# STM32.net
KiCad netlist of a schematic drawn in Altium Designer
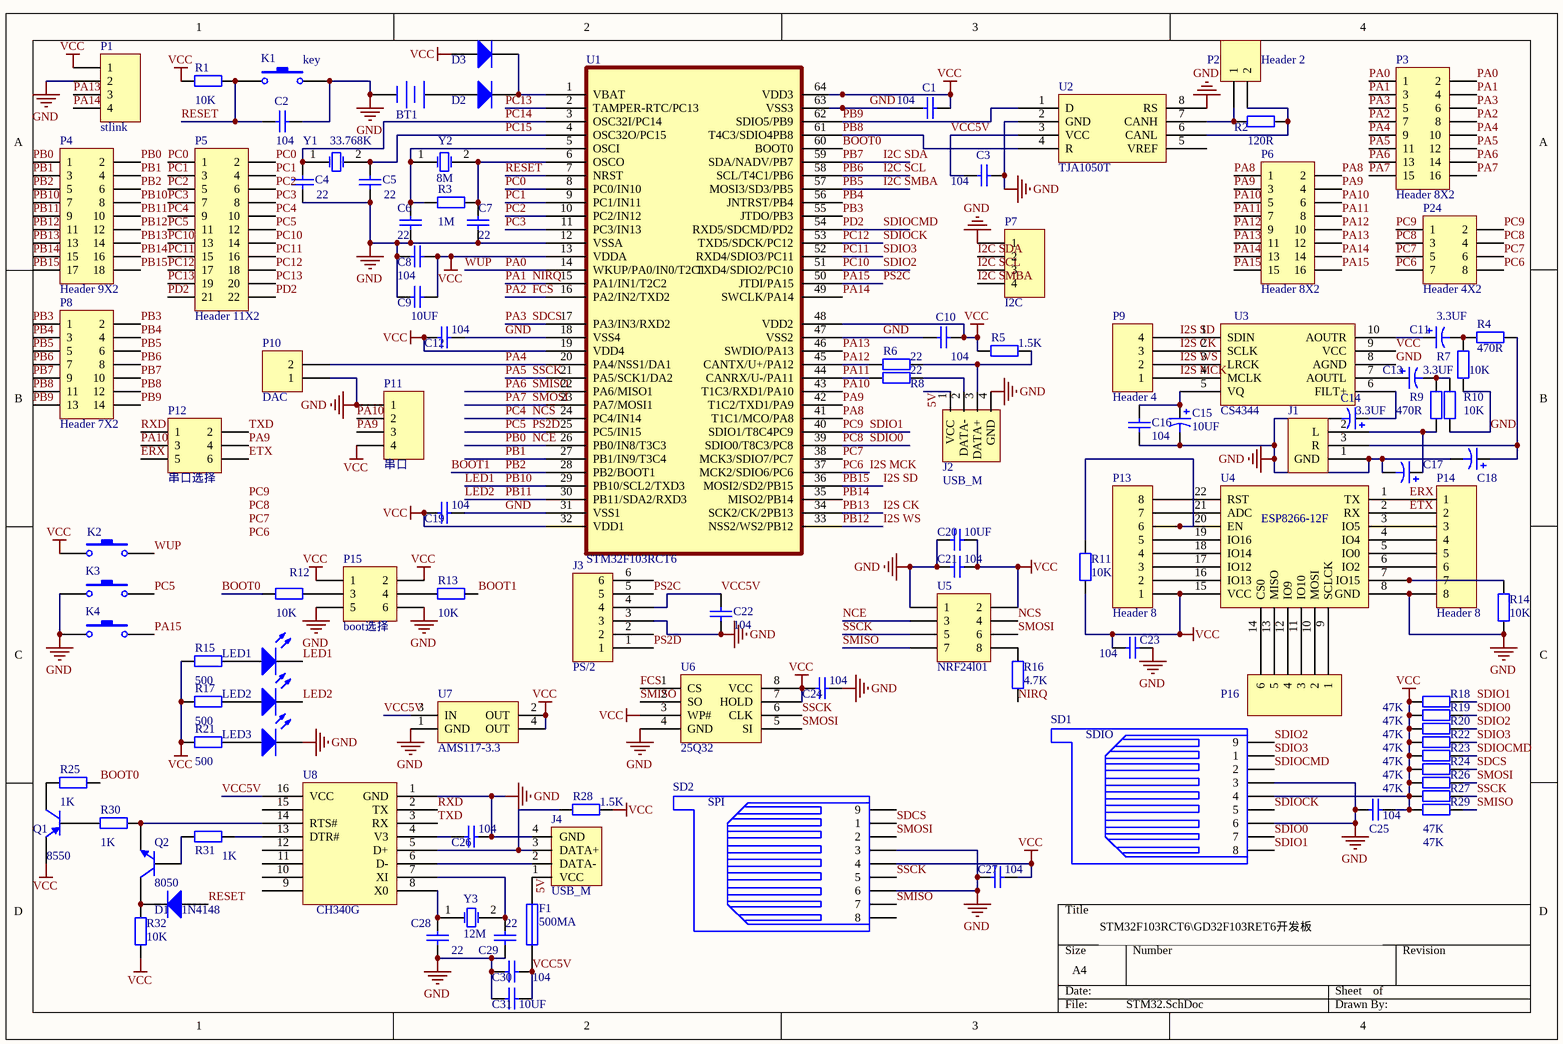
[diagram p0: STM32.SchDoc]

(export (version "E")
  (design (tool "Eeschema 10.0.6"))
  (components
    (comp (ref "BT1") (value "电池") (footprint "电池座") (libsource (lib "SCH封装库") (part "电池")))
    (comp (ref "C1")
      (value "104")
      (footprint "6-0805_N")
      (description "Capacitor")
      (fields (field (name "Comment") "Cap") (field (name "PUBLISHER") "Altium Limited"))
      (libsource (lib "Miscellaneous Devices") (part "Cap"))
    )
    (comp (ref "C2")
      (value "104")
      (footprint "6-0805_N")
      (description "Capacitor")
      (fields (field (name "Comment") "Cap") (field (name "PUBLISHER") "Altium Limited"))
      (libsource (lib "Miscellaneous Devices") (part "Cap"))
    )
    (comp (ref "C3")
      (value "104")
      (footprint "6-0805_N")
      (description "Capacitor")
      (fields (field (name "Comment") "Cap") (field (name "PUBLISHER") "Altium Limited"))
      (libsource (lib "Miscellaneous Devices") (part "Cap"))
    )
    (comp (ref "C4")
      (value "22")
      (footprint "6-0805_N")
      (description "Capacitor")
      (fields (field (name "Comment") "Cap") (field (name "PUBLISHER") "Altium Limited"))
      (libsource (lib "Miscellaneous Devices") (part "Cap"))
    )
    (comp (ref "C5")
      (value "22")
      (footprint "6-0805_N")
      (description "Capacitor")
      (fields (field (name "Comment") "Cap") (field (name "PUBLISHER") "Altium Limited"))
      (libsource (lib "Miscellaneous Devices") (part "Cap"))
    )
    (comp (ref "C6")
      (value "22")
      (footprint "6-0805_N")
      (description "Capacitor")
      (fields (field (name "Comment") "Cap") (field (name "PUBLISHER") "Altium Limited"))
      (libsource (lib "Miscellaneous Devices") (part "Cap"))
    )
    (comp (ref "C7")
      (value "22")
      (footprint "6-0805_N")
      (description "Capacitor")
      (fields (field (name "Comment") "Cap") (field (name "PUBLISHER") "Altium Limited"))
      (libsource (lib "Miscellaneous Devices") (part "Cap"))
    )
    (comp (ref "C8")
      (value "104")
      (footprint "6-0805_N")
      (description "Capacitor")
      (fields (field (name "Comment") "Cap") (field (name "PUBLISHER") "Altium Limited"))
      (libsource (lib "Miscellaneous Devices") (part "Cap"))
    )
    (comp (ref "C9")
      (value "10UF")
      (footprint "6-0805_N")
      (description "Capacitor")
      (fields (field (name "Comment") "Cap") (field (name "PUBLISHER") "Altium Limited"))
      (libsource (lib "Miscellaneous Devices") (part "Cap"))
    )
    (comp (ref "C10")
      (value "104")
      (footprint "6-0805_N")
      (description "Capacitor")
      (fields (field (name "Comment") "Cap") (field (name "PUBLISHER") "Altium Limited"))
      (libsource (lib "Miscellaneous Devices") (part "Cap"))
    )
    (comp (ref "C11")
      (value "3.3UF")
      (footprint "极性电容")
      (description "Polarized Capacitor (Surface Mount)")
      (fields (field (name "Comment") "Cap Pol3") (field (name "PUBLISHER") "Altium Limited"))
      (libsource (lib "Miscellaneous Devices") (part "Cap Pol3"))
    )
    (comp (ref "C12")
      (value "104")
      (footprint "6-0805_N")
      (description "Capacitor")
      (fields (field (name "Comment") "Cap") (field (name "PUBLISHER") "Altium Limited"))
      (libsource (lib "Miscellaneous Devices") (part "Cap"))
    )
    (comp (ref "C13")
      (value "3.3UF")
      (footprint "极性电容")
      (description "Polarized Capacitor (Surface Mount)")
      (fields (field (name "Comment") "Cap Pol3") (field (name "PUBLISHER") "Altium Limited"))
      (libsource (lib "Miscellaneous Devices") (part "Cap Pol3"))
    )
    (comp (ref "C14")
      (value "3.3UF")
      (footprint "极性电容")
      (description "Polarized Capacitor (Surface Mount)")
      (fields (field (name "Comment") "Cap Pol3") (field (name "PUBLISHER") "Altium Limited"))
      (libsource (lib "Miscellaneous Devices") (part "Cap Pol3"))
    )
    (comp (ref "C15")
      (value "10UF")
      (footprint "极性电容")
      (description "Polarized Capacitor (Surface Mount)")
      (fields (field (name "Comment") "Cap Pol3") (field (name "PUBLISHER") "Altium Limited"))
      (libsource (lib "Miscellaneous Devices") (part "Cap Pol3"))
    )
    (comp (ref "C16")
      (value "104")
      (footprint "6-0805_N")
      (description "Capacitor")
      (fields (field (name "Comment") "Cap") (field (name "PUBLISHER") "Altium Limited"))
      (libsource (lib "Miscellaneous Devices") (part "Cap"))
    )
    (comp (ref "C17")
      (value "Cap Pol3")
      (footprint "极性电容")
      (description "Polarized Capacitor (Surface Mount)")
      (fields (field (name "PUBLISHER") "Altium Limited"))
      (libsource (lib "Miscellaneous Devices") (part "Cap Pol3"))
    )
    (comp (ref "C18")
      (value "Cap Pol3")
      (footprint "极性电容")
      (description "Polarized Capacitor (Surface Mount)")
      (fields (field (name "PUBLISHER") "Altium Limited"))
      (libsource (lib "Miscellaneous Devices") (part "Cap Pol3"))
    )
    (comp (ref "C19")
      (value "104")
      (footprint "6-0805_N")
      (description "Capacitor")
      (fields (field (name "Comment") "Cap") (field (name "PUBLISHER") "Altium Limited"))
      (libsource (lib "Miscellaneous Devices") (part "Cap"))
    )
    (comp (ref "C20")
      (value "10UF")
      (footprint "6-0805_N")
      (description "Capacitor")
      (fields (field (name "Comment") "Cap") (field (name "PUBLISHER") "Altium Limited"))
      (libsource (lib "Miscellaneous Devices") (part "Cap"))
    )
    (comp (ref "C21")
      (value "104")
      (footprint "6-0805_N")
      (description "Capacitor")
      (fields (field (name "Comment") "Cap") (field (name "PUBLISHER") "Altium Limited"))
      (libsource (lib "Miscellaneous Devices") (part "Cap"))
    )
    (comp (ref "C22")
      (value "104")
      (footprint "6-0805_N")
      (description "Capacitor")
      (fields (field (name "Comment") "Cap") (field (name "PUBLISHER") "Altium Limited"))
      (libsource (lib "Miscellaneous Devices") (part "Cap"))
    )
    (comp (ref "C23")
      (value "104")
      (footprint "6-0805_N")
      (description "Capacitor")
      (fields (field (name "Comment") "Cap") (field (name "PUBLISHER") "Altium Limited"))
      (libsource (lib "Miscellaneous Devices") (part "Cap"))
    )
    (comp (ref "C24")
      (value "104")
      (footprint "6-0805_N")
      (description "Capacitor")
      (fields (field (name "Comment") "Cap") (field (name "PUBLISHER") "Altium Limited"))
      (libsource (lib "Miscellaneous Devices") (part "Cap"))
    )
    (comp (ref "C25")
      (value "104")
      (footprint "6-0805_N")
      (description "Capacitor")
      (fields (field (name "Comment") "Cap") (field (name "PUBLISHER") "Altium Limited"))
      (libsource (lib "Miscellaneous Devices") (part "Cap"))
    )
    (comp (ref "C26")
      (value "104")
      (footprint "6-0805_N")
      (description "Capacitor")
      (fields (field (name "Comment") "Cap") (field (name "PUBLISHER") "Altium Limited"))
      (libsource (lib "Miscellaneous Devices") (part "Cap"))
    )
    (comp (ref "C27")
      (value "104")
      (footprint "6-0805_N")
      (description "Capacitor")
      (fields (field (name "Comment") "Cap") (field (name "PUBLISHER") "Altium Limited"))
      (libsource (lib "Miscellaneous Devices") (part "Cap"))
    )
    (comp (ref "C28")
      (value "22")
      (footprint "6-0805_N")
      (description "Capacitor")
      (fields (field (name "Comment") "Cap") (field (name "PUBLISHER") "Altium Limited"))
      (libsource (lib "Miscellaneous Devices") (part "Cap"))
    )
    (comp (ref "C29")
      (value "22")
      (footprint "6-0805_N")
      (description "Capacitor")
      (fields (field (name "Comment") "Cap") (field (name "PUBLISHER") "Altium Limited"))
      (libsource (lib "Miscellaneous Devices") (part "Cap"))
    )
    (comp (ref "C30")
      (value "104")
      (footprint "6-0805_N")
      (description "Capacitor")
      (fields (field (name "Comment") "Cap") (field (name "PUBLISHER") "Altium Limited"))
      (libsource (lib "Miscellaneous Devices") (part "Cap"))
    )
    (comp (ref "C31")
      (value "10UF")
      (footprint "6-0805_N")
      (description "Capacitor")
      (fields (field (name "Comment") "Cap") (field (name "PUBLISHER") "Altium Limited"))
      (libsource (lib "Miscellaneous Devices") (part "Cap"))
    )
    (comp (ref "D1")
      (value "1N4148")
      (footprint "1206")
      (description "High Conductance Fast Diode")
      (fields (field (name "PUBLISHER") "Altium Limited"))
      (libsource (lib "Miscellaneous Devices") (part "Diode 1N4148"))
    )
    (comp (ref "D2")
      (value "1N4148")
      (footprint "1206")
      (description "High Conductance Fast Diode")
      (fields (field (name "PUBLISHER") "Altium Limited"))
      (libsource (lib "Miscellaneous Devices") (part "Diode 1N4148"))
    )
    (comp (ref "D3")
      (value "1N4148")
      (footprint "1206")
      (description "High Conductance Fast Diode")
      (fields (field (name "PUBLISHER") "Altium Limited"))
      (libsource (lib "Miscellaneous Devices") (part "Diode 1N4148"))
    )
    (comp (ref "F1")
      (value "500MA")
      (footprint "1812")
      (description "Fuse")
      (fields (field (name "PUBLISHER") "Altium Limited"))
      (libsource (lib "Miscellaneous Devices") (part "Fuse 1"))
    )
    (comp (ref "J1") (value "Component_1") (footprint "耳机座") (libsource (lib "耳机") (part "Component_1")))
    (comp (ref "J2") (value "USB_M") (footprint "USB MICRO") (libsource (lib "") (part "USB_M_1")))
    (comp (ref "J3") (value "PS/2") (footprint "PS/2") (libsource (lib "SCH封装库") (part "PS/2")))
    (comp (ref "J4") (value "USB_M") (footprint "USB MICRO") (libsource (lib "SCH封装库") (part "USB_M")))
    (comp (ref "K1") (value "key") (footprint "按键") (libsource (lib "SCH封装库") (part "按键")))
    (comp (ref "K2") (value "按键") (footprint "按键") (libsource (lib "SCH封装库") (part "按键")))
    (comp (ref "K3") (value "按键") (footprint "按键") (libsource (lib "SCH封装库") (part "按键")))
    (comp (ref "K4") (value "按键") (footprint "按键") (libsource (lib "SCH封装库") (part "按键")))
    (comp (ref "LED1") (value "LED") (footprint "6-0805_N") (libsource (lib "SCH封装库") (part "发光二极管")))
    (comp (ref "LED2") (value "LED") (footprint "6-0805_N") (libsource (lib "SCH封装库") (part "发光二极管")))
    (comp (ref "LED3") (value "LED") (footprint "6-0805_N") (libsource (lib "SCH封装库") (part "发光二极管")))
    (comp (ref "P1")
      (value "stlink")
      (footprint "HDR1X4")
      (description "Header, 4-Pin")
      (fields (field (name "PUBLISHER") "Altium Limited"))
      (libsource (lib "Miscellaneous Connectors") (part "Header 4"))
    )
    (comp (ref "P2")
      (value "Header 2")
      (footprint "HDR1X2")
      (description "Header, 2-Pin")
      (fields (field (name "PUBLISHER") "Altium Limited"))
      (libsource (lib "") (part "Header 2_1"))
    )
    (comp (ref "P3")
      (value "Header 8X2")
      (footprint "HDR2X8")
      (description "Header, 8-Pin, Dual row")
      (fields (field (name "PUBLISHER") "Altium Limited"))
      (libsource (lib "Miscellaneous Connectors") (part "Header 8X2"))
    )
    (comp (ref "P4")
      (value "Header 9X2")
      (footprint "HDR2X9")
      (description "Header, 9-Pin, Dual row")
      (fields (field (name "PUBLISHER") "Altium Limited"))
      (libsource (lib "Miscellaneous Connectors") (part "Header 9X2"))
    )
    (comp (ref "P5")
      (value "Header 11X2")
      (footprint "HDR2X11")
      (description "Header, 11-Pin, Dual row")
      (fields (field (name "PUBLISHER") "Altium Limited"))
      (libsource (lib "Miscellaneous Connectors") (part "Header 11X2"))
    )
    (comp (ref "P6")
      (value "Header 8X2")
      (footprint "HDR2X8")
      (description "Header, 8-Pin, Dual row")
      (fields (field (name "PUBLISHER") "Altium Limited"))
      (libsource (lib "Miscellaneous Connectors") (part "Header 8X2"))
    )
    (comp (ref "P7")
      (value "I2C")
      (footprint "HDR1X4")
      (description "Header, 4-Pin")
      (fields (field (name "PUBLISHER") "Altium Limited"))
      (libsource (lib "Miscellaneous Connectors") (part "Header 4"))
    )
    (comp (ref "P8")
      (value "Header 7X2")
      (footprint "HDR2X7")
      (description "Header, 7-Pin, Dual row")
      (fields (field (name "PUBLISHER") "Altium Limited"))
      (libsource (lib "Miscellaneous Connectors") (part "Header 7X2"))
    )
    (comp (ref "P9")
      (value "Header 4")
      (footprint "HDR1X4")
      (description "Header, 4-Pin")
      (fields (field (name "PUBLISHER") "Altium Limited"))
      (libsource (lib "") (part "Header 4_1"))
    )
    (comp (ref "P10")
      (value "DAC")
      (footprint "HDR1X2")
      (description "Header, 2-Pin")
      (fields (field (name "PUBLISHER") "Altium Limited"))
      (libsource (lib "Miscellaneous Connectors") (part "Header 2"))
    )
    (comp (ref "P11")
      (value "串口")
      (footprint "HDR1X4")
      (description "Header, 4-Pin")
      (fields (field (name "PUBLISHER") "Altium Limited"))
      (libsource (lib "Miscellaneous Connectors") (part "Header 4"))
    )
    (comp (ref "P12")
      (value "串口选择")
      (footprint "HDR2X3")
      (description "Header, 3-Pin, Dual row")
      (fields (field (name "PUBLISHER") "Altium Limited"))
      (libsource (lib "Miscellaneous Connectors") (part "Header 3X2"))
    )
    (comp (ref "P13")
      (value "Header 8")
      (footprint "HDR1X8")
      (description "Header, 8-Pin")
      (fields (field (name "PUBLISHER") "Altium Limited"))
      (libsource (lib "Miscellaneous Connectors") (part "Header 8"))
    )
    (comp (ref "P14")
      (value "Header 8")
      (footprint "HDR1X8")
      (description "Header, 8-Pin")
      (fields (field (name "PUBLISHER") "Altium Limited"))
      (libsource (lib "") (part "Header 8_1"))
    )
    (comp (ref "P15")
      (value "boot选择")
      (footprint "HDR2X3")
      (description "Header, 3-Pin, Dual row")
      (fields (field (name "PUBLISHER") "Altium Limited"))
      (libsource (lib "Miscellaneous Connectors") (part "Header 3X2"))
    )
    (comp (ref "P16")
      (value "Header 6")
      (footprint "HDR1X6")
      (description "Header, 6-Pin")
      (fields (field (name "PUBLISHER") "Altium Limited"))
      (libsource (lib "Miscellaneous Connectors") (part "Header 6"))
    )
    (comp (ref "P24")
      (value "Header 4X2")
      (footprint "HDR2X4")
      (description "Header, 4-Pin, Dual row")
      (fields (field (name "PUBLISHER") "Altium Limited"))
      (libsource (lib "Miscellaneous Connectors") (part "Header 4X2"))
    )
    (comp (ref "Q1")
      (value "8550")
      (footprint "SOT-23B_N")
      (description "PNP Bipolar Transistor")
      (fields (field (name "PUBLISHER") "Altium Limited"))
      (libsource (lib "Miscellaneous Devices") (part "PNP"))
    )
    (comp (ref "Q2")
      (value "8050")
      (footprint "SOT-23B_N")
      (description "NPN Bipolar Transistor")
      (fields (field (name "PUBLISHER") "Altium Limited"))
      (libsource (lib "Miscellaneous Devices") (part "NPN"))
    )
    (comp (ref "R1")
      (value "10K")
      (footprint "6-0805_N")
      (description "Resistor")
      (fields (field (name "Comment") "Res2") (field (name "PUBLISHER") "Altium Limited"))
      (libsource (lib "Miscellaneous Devices") (part "Res2"))
    )
    (comp (ref "R2")
      (value "120R")
      (footprint "6-0805_N")
      (description "Resistor")
      (fields (field (name "Comment") "Res2") (field (name "PUBLISHER") "Altium Limited"))
      (libsource (lib "Miscellaneous Devices") (part "Res2"))
    )
    (comp (ref "R3")
      (value "1M")
      (footprint "6-0805_N")
      (description "Resistor")
      (fields (field (name "Comment") "Res2") (field (name "PUBLISHER") "Altium Limited"))
      (libsource (lib "Miscellaneous Devices") (part "Res2"))
    )
    (comp (ref "R4")
      (value "470R")
      (footprint "6-0805_N")
      (description "Resistor")
      (fields (field (name "Comment") "Res2") (field (name "PUBLISHER") "Altium Limited"))
      (libsource (lib "") (part "Res2_3"))
    )
    (comp (ref "R5")
      (value "1.5K")
      (footprint "6-0805_N")
      (description "Resistor")
      (fields (field (name "Comment") "Res2") (field (name "PUBLISHER") "Altium Limited"))
      (libsource (lib "Miscellaneous Devices") (part "Res2"))
    )
    (comp (ref "R6")
      (value "22")
      (footprint "6-0805_N")
      (description "Resistor")
      (fields (field (name "Comment") "Res2") (field (name "PUBLISHER") "Altium Limited"))
      (libsource (lib "Miscellaneous Devices") (part "Res2"))
    )
    (comp (ref "R7")
      (value "10K")
      (footprint "6-0805_N")
      (description "Resistor")
      (fields (field (name "Comment") "Res2") (field (name "PUBLISHER") "Altium Limited"))
      (libsource (lib "") (part "Res2_1"))
    )
    (comp (ref "R8")
      (value "22")
      (footprint "6-0805_N")
      (description "Resistor")
      (fields (field (name "Comment") "Res2") (field (name "PUBLISHER") "Altium Limited"))
      (libsource (lib "Miscellaneous Devices") (part "Res2"))
    )
    (comp (ref "R9")
      (value "470R")
      (footprint "6-0805_N")
      (description "Resistor")
      (fields (field (name "Comment") "Res2") (field (name "PUBLISHER") "Altium Limited"))
      (libsource (lib "") (part "Res2_2"))
    )
    (comp (ref "R10")
      (value "10K")
      (footprint "6-0805_N")
      (description "Resistor")
      (fields (field (name "Comment") "Res2") (field (name "PUBLISHER") "Altium Limited"))
      (libsource (lib "") (part "Res2_1"))
    )
    (comp (ref "R11")
      (value "10K")
      (footprint "6-0805_N")
      (description "Resistor")
      (fields (field (name "Comment") "Res2") (field (name "PUBLISHER") "Altium Limited"))
      (libsource (lib "") (part "Res2_1"))
    )
    (comp (ref "R12")
      (value "10K")
      (footprint "6-0805_N")
      (description "Resistor")
      (fields (field (name "Comment") "Res2") (field (name "PUBLISHER") "Altium Limited"))
      (libsource (lib "Miscellaneous Devices") (part "Res2"))
    )
    (comp (ref "R13")
      (value "10K")
      (footprint "6-0805_N")
      (description "Resistor")
      (fields (field (name "Comment") "Res2") (field (name "PUBLISHER") "Altium Limited"))
      (libsource (lib "Miscellaneous Devices") (part "Res2"))
    )
    (comp (ref "R14")
      (value "10K")
      (footprint "6-0805_N")
      (description "Resistor")
      (fields (field (name "Comment") "Res2") (field (name "PUBLISHER") "Altium Limited"))
      (libsource (lib "") (part "Res2_1"))
    )
    (comp (ref "R15")
      (value "500")
      (footprint "6-0805_N")
      (description "Resistor")
      (fields (field (name "Comment") "Res2") (field (name "PUBLISHER") "Altium Limited"))
      (libsource (lib "Miscellaneous Devices") (part "Res2"))
    )
    (comp (ref "R16")
      (value "4.7K")
      (footprint "6-0805_N")
      (description "Resistor")
      (fields (field (name "Comment") "Res2") (field (name "PUBLISHER") "Altium Limited"))
      (libsource (lib "") (part "Res2_2"))
    )
    (comp (ref "R17")
      (value "500")
      (footprint "6-0805_N")
      (description "Resistor")
      (fields (field (name "Comment") "Res2") (field (name "PUBLISHER") "Altium Limited"))
      (libsource (lib "Miscellaneous Devices") (part "Res2"))
    )
    (comp (ref "R18")
      (value "47K")
      (footprint "6-0805_N")
      (description "Resistor")
      (fields (field (name "Comment") "Res2") (field (name "PUBLISHER") "Altium Limited"))
      (libsource (lib "Miscellaneous Devices") (part "Res2"))
    )
    (comp (ref "R19")
      (value "47K")
      (footprint "6-0805_N")
      (description "Resistor")
      (fields (field (name "Comment") "Res2") (field (name "PUBLISHER") "Altium Limited"))
      (libsource (lib "Miscellaneous Devices") (part "Res2"))
    )
    (comp (ref "R20")
      (value "47K")
      (footprint "6-0805_N")
      (description "Resistor")
      (fields (field (name "Comment") "Res2") (field (name "PUBLISHER") "Altium Limited"))
      (libsource (lib "Miscellaneous Devices") (part "Res2"))
    )
    (comp (ref "R21")
      (value "500")
      (footprint "6-0805_N")
      (description "Resistor")
      (fields (field (name "Comment") "Res2") (field (name "PUBLISHER") "Altium Limited"))
      (libsource (lib "Miscellaneous Devices") (part "Res2"))
    )
    (comp (ref "R22")
      (value "47K")
      (footprint "6-0805_N")
      (description "Resistor")
      (fields (field (name "Comment") "Res2") (field (name "PUBLISHER") "Altium Limited"))
      (libsource (lib "Miscellaneous Devices") (part "Res2"))
    )
    (comp (ref "R23")
      (value "47K")
      (footprint "6-0805_N")
      (description "Resistor")
      (fields (field (name "Comment") "Res2") (field (name "PUBLISHER") "Altium Limited"))
      (libsource (lib "Miscellaneous Devices") (part "Res2"))
    )
    (comp (ref "R24")
      (value "47K")
      (footprint "6-0805_N")
      (description "Resistor")
      (fields (field (name "Comment") "Res2") (field (name "PUBLISHER") "Altium Limited"))
      (libsource (lib "Miscellaneous Devices") (part "Res2"))
    )
    (comp (ref "R25")
      (value "1K")
      (footprint "6-0805_N")
      (description "Resistor")
      (fields (field (name "Comment") "Res2") (field (name "PUBLISHER") "Altium Limited"))
      (libsource (lib "Miscellaneous Devices") (part "Res2"))
    )
    (comp (ref "R26")
      (value "47K")
      (footprint "6-0805_N")
      (description "Resistor")
      (fields (field (name "Comment") "Res2") (field (name "PUBLISHER") "Altium Limited"))
      (libsource (lib "Miscellaneous Devices") (part "Res2"))
    )
    (comp (ref "R27")
      (value "47K")
      (footprint "6-0805_N")
      (description "Resistor")
      (fields (field (name "Comment") "Res2") (field (name "PUBLISHER") "Altium Limited"))
      (libsource (lib "Miscellaneous Devices") (part "Res2"))
    )
    (comp (ref "R28")
      (value "1.5K")
      (footprint "6-0805_N")
      (description "Resistor")
      (fields (field (name "Comment") "Res2") (field (name "PUBLISHER") "Altium Limited"))
      (libsource (lib "Miscellaneous Devices") (part "Res2"))
    )
    (comp (ref "R29")
      (value "47K")
      (footprint "6-0805_N")
      (description "Resistor")
      (fields (field (name "Comment") "Res2") (field (name "PUBLISHER") "Altium Limited"))
      (libsource (lib "Miscellaneous Devices") (part "Res2"))
    )
    (comp (ref "R30")
      (value "1K")
      (footprint "6-0805_N")
      (description "Resistor")
      (fields (field (name "Comment") "Res2") (field (name "PUBLISHER") "Altium Limited"))
      (libsource (lib "Miscellaneous Devices") (part "Res2"))
    )
    (comp (ref "R31")
      (value "1K")
      (footprint "6-0805_N")
      (description "Resistor")
      (fields (field (name "Comment") "Res2") (field (name "PUBLISHER") "Altium Limited"))
      (libsource (lib "Miscellaneous Devices") (part "Res2"))
    )
    (comp (ref "R32")
      (value "10K")
      (footprint "6-0805_N")
      (description "Resistor")
      (fields (field (name "Comment") "Res2") (field (name "PUBLISHER") "Altium Limited"))
      (libsource (lib "") (part "Res2_1"))
    )
    (comp (ref "SD1")
      (value "PJS008-2000")
      (footprint "TFCARD-M")
      (fields (field (name "A") "SDIO"))
      (libsource (lib "MB525") (part "SMS016AFA5E"))
    )
    (comp (ref "SD2")
      (value "PJS008-2000")
      (footprint "SDCARD_A")
      (fields (field (name "A") "SPI"))
      (libsource (lib "MB525") (part "SMS016AFA5E"))
    )
    (comp (ref "U1")
      (value "STM32F103RCT6")
      (footprint "LQFP64")
      (libsource (lib "STM32SCH") (part "STM32F103RDT6"))
    )
    (comp (ref "U2") (value "TJA1050T") (footprint "SO8_M") (libsource (lib "TJA1050") (part "Component_1")))
    (comp (ref "U3")
      (value "CS4344")
      (footprint "TSSOP110_s")
      (libsource (lib "CS4344") (part "Component_1"))
    )
    (comp (ref "U4")
      (value "Component_1")
      (footprint "ESP_12_f")
      (libsource (lib "ESP8266") (part "Component_1"))
    )
    (comp (ref "U5")
      (value "NRF24l01")
      (footprint "HDR2X4")
      (description "Header, 4-Pin, Dual row")
      (fields (field (name "PUBLISHER") "Altium Limited"))
      (libsource (lib "Miscellaneous Connectors") (part "Header 4X2"))
    )
    (comp (ref "U6") (value "25Q32") (footprint "SO8_M") (libsource (lib "25Q32") (part "Component_1")))
    (comp (ref "U7")
      (value "AMS117-3.3")
      (footprint "ZZ311")
      (description "800mA and 1A Low Dropout Positive Regulator 2.85V, 3.3V, 5V, and Adjustable")
      (fields (field (name "PUBLISHER") "Altium Limited"))
      (libsource (lib "BB Power Mgt Voltage Regulator") (part "REG1117-3.3"))
    )
    (comp (ref "U8")
      (value "Component_1")
      (footprint "SO-16_M")
      (libsource (lib "CH340") (part "Component_1"))
    )
    (comp (ref "Y1") (value "33.768K") (footprint "SIP2") (libsource (lib "SCH封装库") (part "晶振")))
    (comp (ref "Y2") (value "8M") (footprint "晶振") (libsource (lib "SCH封装库") (part "晶振")))
    (comp (ref "Y3") (value "12M") (footprint "晶振") (libsource (lib "SCH封装库") (part "晶振")))
  )
  (nets
    (net (code "1") (name "/5V") (class "Default")
      (node (ref "F1") (pin "2") (pinfunction "2_2") (pintype "passive"))
      (node (ref "J2") (pin "1") (pinfunction "VCC_1") (pintype "passive"))
      (node (ref "J4") (pin "1") (pinfunction "VCC_1") (pintype "passive"))
    )
    (net (code "2") (name "/BOOT0") (class "Default")
      (node (ref "R12") (pin "1") (pinfunction "1_1") (pintype "passive"))
      (node (ref "R25") (pin "2") (pinfunction "2_2") (pintype "passive"))
      (node (ref "U1") (pin "60") (pinfunction "BOOT0_60") (pintype "passive"))
    )
    (net (code "3") (name "/BOOT1") (class "Default")
      (node (ref "P4") (pin "5") (pinfunction "5_5") (pintype "passive"))
      (node (ref "P4") (pin "6") (pinfunction "6_6") (pintype "passive"))
      (node (ref "R13") (pin "2") (pinfunction "2_2") (pintype "passive"))
      (node (ref "U1") (pin "28") (pinfunction "PB2/BOOT1_28") (pintype "passive"))
    )
    (net (code "4") (name "/ERX") (class "Default")
      (node (ref "P12") (pin "5") (pinfunction "5_5") (pintype "passive"))
      (node (ref "P14") (pin "1") (pinfunction "1_1") (pintype "passive"))
      (node (ref "U4") (pin "1") (pinfunction "TX_1") (pintype "passive"))
    )
    (net (code "5") (name "/ETX") (class "Default")
      (node (ref "P12") (pin "6") (pinfunction "6_6") (pintype "passive"))
      (node (ref "P14") (pin "2") (pinfunction "2_2") (pintype "passive"))
      (node (ref "U4") (pin "2") (pinfunction "RX_2") (pintype "passive"))
    )
    (net (code "6") (name "/FCS") (class "Default")
      (node (ref "P3") (pin "7") (pinfunction "7_7") (pintype "passive"))
      (node (ref "P3") (pin "8") (pinfunction "8_8") (pintype "passive"))
      (node (ref "U1") (pin "16") (pinfunction "PA2/IN2/TXD2_16") (pintype "passive"))
      (node (ref "U6") (pin "1") (pinfunction "CS_1") (pintype "passive"))
    )
    (net (code "7") (name "/I2C SCL") (class "Default")
      (node (ref "P7") (pin "3") (pinfunction "3_3") (pintype "passive"))
      (node (ref "P8") (pin "7") (pinfunction "7_7") (pintype "passive"))
      (node (ref "P8") (pin "8") (pinfunction "8_8") (pintype "passive"))
      (node (ref "U1") (pin "58") (pinfunction "SCL/T4C1/PB6_58") (pintype "passive"))
    )
    (net (code "8") (name "/I2C SDA") (class "Default")
      (node (ref "P7") (pin "2") (pinfunction "2_2") (pintype "passive"))
      (node (ref "P8") (pin "10") (pinfunction "10_10") (pintype "passive"))
      (node (ref "P8") (pin "9") (pinfunction "9_9") (pintype "passive"))
      (node (ref "U1") (pin "59") (pinfunction "SDA/NADV/PB7_59") (pintype "passive"))
    )
    (net (code "9") (name "/I2C SMBA") (class "Default")
      (node (ref "P7") (pin "4") (pinfunction "4_4") (pintype "passive"))
      (node (ref "P8") (pin "5") (pinfunction "5_5") (pintype "passive"))
      (node (ref "P8") (pin "6") (pinfunction "6_6") (pintype "passive"))
      (node (ref "U1") (pin "57") (pinfunction "MOSI3/SD3/PB5_57") (pintype "passive"))
    )
    (net (code "10") (name "/I2S CK") (class "Default")
      (node (ref "P4") (pin "13") (pinfunction "13_13") (pintype "passive"))
      (node (ref "P4") (pin "14") (pinfunction "14_14") (pintype "passive"))
      (node (ref "P9") (pin "3") (pinfunction "3_3") (pintype "passive"))
      (node (ref "U1") (pin "34") (pinfunction "SCK2/CK/2PB13_34") (pintype "passive"))
      (node (ref "U3") (pin "2") (pinfunction "SCLK_2") (pintype "passive"))
    )
    (net (code "11") (name "/I2S MCK") (class "Default")
      (node (ref "P24") (pin "7") (pinfunction "7_7") (pintype "passive"))
      (node (ref "P24") (pin "8") (pinfunction "8_8") (pintype "passive"))
      (node (ref "P9") (pin "1") (pinfunction "1_1") (pintype "passive"))
      (node (ref "U1") (pin "37") (pinfunction "MCK2/SDIO6/PC6_37") (pintype "passive"))
      (node (ref "U3") (pin "4") (pinfunction "MCLK_4") (pintype "passive"))
    )
    (net (code "12") (name "/I2S SD") (class "Default")
      (node (ref "P4") (pin "17") (pinfunction "17_17") (pintype "passive"))
      (node (ref "P4") (pin "18") (pinfunction "18_18") (pintype "passive"))
      (node (ref "P9") (pin "4") (pinfunction "4_4") (pintype "passive"))
      (node (ref "U1") (pin "36") (pinfunction "MOSI2/SD2/PB15_36") (pintype "passive"))
      (node (ref "U3") (pin "1") (pinfunction "SDIN_1") (pintype "passive"))
    )
    (net (code "13") (name "/I2S WS") (class "Default")
      (node (ref "P4") (pin "11") (pinfunction "11_11") (pintype "passive"))
      (node (ref "P4") (pin "12") (pinfunction "12_12") (pintype "passive"))
      (node (ref "P9") (pin "2") (pinfunction "2_2") (pintype "passive"))
      (node (ref "U1") (pin "33") (pinfunction "NSS2/WS2/PB12_33") (pintype "passive"))
      (node (ref "U3") (pin "3") (pinfunction "LRCK_3") (pintype "passive"))
    )
    (net (code "14") (name "/LED1") (class "Default")
      (node (ref "LED1") (pin "2") (pinfunction "2_2") (pintype "passive"))
      (node (ref "P4") (pin "7") (pinfunction "7_7") (pintype "passive"))
      (node (ref "P4") (pin "8") (pinfunction "8_8") (pintype "passive"))
      (node (ref "U1") (pin "29") (pinfunction "PB10/SCL2/TXD3_29") (pintype "passive"))
    )
    (net (code "15") (name "/LED2") (class "Default")
      (node (ref "LED2") (pin "2") (pinfunction "2_2") (pintype "passive"))
      (node (ref "P4") (pin "10") (pinfunction "10_10") (pintype "passive"))
      (node (ref "P4") (pin "9") (pinfunction "9_9") (pintype "passive"))
      (node (ref "U1") (pin "30") (pinfunction "PB11/SDA2/RXD3_30") (pintype "passive"))
    )
    (net (code "16") (name "/NCE") (class "Default")
      (node (ref "P4") (pin "1") (pinfunction "1_1") (pintype "passive"))
      (node (ref "P4") (pin "2") (pinfunction "2_2") (pintype "passive"))
      (node (ref "U1") (pin "26") (pinfunction "PB0/IN8/T3C3_26") (pintype "passive"))
      (node (ref "U5") (pin "3") (pinfunction "3_3") (pintype "passive"))
    )
    (net (code "17") (name "/NCS") (class "Default")
      (node (ref "P5") (pin "10") (pinfunction "10_10") (pintype "passive"))
      (node (ref "P5") (pin "9") (pinfunction "9_9") (pintype "passive"))
      (node (ref "U1") (pin "24") (pinfunction "PC4/IN14_24") (pintype "passive"))
      (node (ref "U5") (pin "4") (pinfunction "4_4") (pintype "passive"))
    )
    (net (code "18") (name "/NIRQ") (class "Default")
      (node (ref "P3") (pin "3") (pinfunction "3_3") (pintype "passive"))
      (node (ref "P3") (pin "4") (pinfunction "4_4") (pintype "passive"))
      (node (ref "R16") (pin "2") (pinfunction "2_2") (pintype "passive"))
      (node (ref "U1") (pin "15") (pinfunction "PA1/IN1/T2C2_15") (pintype "passive"))
    )
    (net (code "19") (name "/PA0") (class "Default")
      (node (ref "K2") (pin "2") (pinfunction "2_2") (pintype "passive"))
      (node (ref "P3") (pin "1") (pinfunction "1_1") (pintype "passive"))
      (node (ref "P3") (pin "2") (pinfunction "2_2") (pintype "passive"))
      (node (ref "U1") (pin "14") (pinfunction "WKUP/PA0/IN0/T2C1_14") (pintype "passive"))
    )
    (net (code "20") (name "/PA3") (class "Default")
      (node (ref "P3") (pin "5") (pinfunction "5_5") (pintype "passive"))
      (node (ref "P3") (pin "6") (pinfunction "6_6") (pintype "passive"))
      (node (ref "R24") (pin "2") (pinfunction "2_2") (pintype "passive"))
      (node (ref "SD2") (pin "1") (pinfunction "1_1") (pintype "passive"))
      (node (ref "U1") (pin "17") (pinfunction "PA3/IN3/RXD2_17") (pintype "passive"))
    )
    (net (code "21") (name "/PA4") (class "Default")
      (node (ref "P10") (pin "2") (pinfunction "2_2") (pintype "passive"))
      (node (ref "P3") (pin "10") (pinfunction "10_10") (pintype "passive"))
      (node (ref "P3") (pin "9") (pinfunction "9_9") (pintype "passive"))
      (node (ref "U1") (pin "20") (pinfunction "PA4/NSS1/DA1_20") (pintype "passive"))
    )
    (net (code "22") (name "/PA5") (class "Default")
      (node (ref "P3") (pin "11") (pinfunction "11_11") (pintype "passive"))
      (node (ref "P3") (pin "12") (pinfunction "12_12") (pintype "passive"))
      (node (ref "R27") (pin "2") (pinfunction "2_2") (pintype "passive"))
      (node (ref "SD2") (pin "5") (pinfunction "5_5") (pintype "passive"))
      (node (ref "U1") (pin "21") (pinfunction "PA5/SCK1/DA2_21") (pintype "passive"))
      (node (ref "U5") (pin "5") (pinfunction "5_5") (pintype "passive"))
      (node (ref "U6") (pin "6") (pinfunction "CLK_6") (pintype "passive"))
    )
    (net (code "23") (name "/PA6") (class "Default")
      (node (ref "P3") (pin "13") (pinfunction "13_13") (pintype "passive"))
      (node (ref "P3") (pin "14") (pinfunction "14_14") (pintype "passive"))
      (node (ref "R29") (pin "2") (pinfunction "2_2") (pintype "passive"))
      (node (ref "SD2") (pin "7") (pinfunction "7_7") (pintype "passive"))
      (node (ref "U1") (pin "22") (pinfunction "PA6/MISO1_22") (pintype "passive"))
      (node (ref "U5") (pin "7") (pinfunction "7_7") (pintype "passive"))
      (node (ref "U6") (pin "2") (pinfunction "SO_2") (pintype "passive"))
    )
    (net (code "24") (name "/PA7") (class "Default")
      (node (ref "P3") (pin "15") (pinfunction "15_15") (pintype "passive"))
      (node (ref "P3") (pin "16") (pinfunction "16_16") (pintype "passive"))
      (node (ref "R26") (pin "2") (pinfunction "2_2") (pintype "passive"))
      (node (ref "SD2") (pin "2") (pinfunction "2_2") (pintype "passive"))
      (node (ref "U1") (pin "23") (pinfunction "PA7/MOSI1_23") (pintype "passive"))
      (node (ref "U5") (pin "6") (pinfunction "6_6") (pintype "passive"))
      (node (ref "U6") (pin "5") (pinfunction "SI_5") (pintype "passive"))
    )
    (net (code "25") (name "/PA8") (class "Default")
      (node (ref "P6") (pin "1") (pinfunction "1_1") (pintype "passive"))
      (node (ref "P6") (pin "2") (pinfunction "2_2") (pintype "passive"))
      (node (ref "U1") (pin "41") (pinfunction "T1C1/MCO/PA8_41") (pintype "passive"))
    )
    (net (code "26") (name "/PA9") (class "Default")
      (node (ref "P11") (pin "3") (pinfunction "3_3") (pintype "passive"))
      (node (ref "P12") (pin "4") (pinfunction "4_4") (pintype "passive"))
      (node (ref "P6") (pin "3") (pinfunction "3_3") (pintype "passive"))
      (node (ref "P6") (pin "4") (pinfunction "4_4") (pintype "passive"))
      (node (ref "U1") (pin "42") (pinfunction "T1C2/TXD1/PA9_42") (pintype "passive"))
    )
    (net (code "27") (name "/PA10") (class "Default")
      (node (ref "P11") (pin "2") (pinfunction "2_2") (pintype "passive"))
      (node (ref "P12") (pin "3") (pinfunction "3_3") (pintype "passive"))
      (node (ref "P6") (pin "5") (pinfunction "5_5") (pintype "passive"))
      (node (ref "P6") (pin "6") (pinfunction "6_6") (pintype "passive"))
      (node (ref "U1") (pin "43") (pinfunction "T1C3/RXD1/PA10_43") (pintype "passive"))
    )
    (net (code "28") (name "/PA11") (class "Default")
      (node (ref "P6") (pin "7") (pinfunction "7_7") (pintype "passive"))
      (node (ref "P6") (pin "8") (pinfunction "8_8") (pintype "passive"))
      (node (ref "R8") (pin "1") (pinfunction "1_1") (pintype "passive"))
      (node (ref "U1") (pin "44") (pinfunction "CANRX/U-/PA11_44") (pintype "passive"))
    )
    (net (code "29") (name "/PA12") (class "Default")
      (node (ref "P6") (pin "10") (pinfunction "10_10") (pintype "passive"))
      (node (ref "P6") (pin "9") (pinfunction "9_9") (pintype "passive"))
      (node (ref "R6") (pin "1") (pinfunction "1_1") (pintype "passive"))
      (node (ref "U1") (pin "45") (pinfunction "CANTX/U+/PA12_45") (pintype "passive"))
    )
    (net (code "30") (name "/PA13") (class "Default")
      (node (ref "P1") (pin "3") (pinfunction "3_3") (pintype "passive"))
      (node (ref "P6") (pin "11") (pinfunction "11_11") (pintype "passive"))
      (node (ref "P6") (pin "12") (pinfunction "12_12") (pintype "passive"))
      (node (ref "U1") (pin "46") (pinfunction "SWDIO/PA13_46") (pintype "passive"))
    )
    (net (code "31") (name "/PA14") (class "Default")
      (node (ref "P1") (pin "4") (pinfunction "4_4") (pintype "passive"))
      (node (ref "P6") (pin "13") (pinfunction "13_13") (pintype "passive"))
      (node (ref "P6") (pin "14") (pinfunction "14_14") (pintype "passive"))
      (node (ref "U1") (pin "49") (pinfunction "SWCLK/PA14_49") (pintype "passive"))
    )
    (net (code "32") (name "/PA15") (class "Default")
      (node (ref "J3") (pin "5") (pinfunction "5_5") (pintype "passive"))
      (node (ref "K4") (pin "2") (pinfunction "2_2") (pintype "passive"))
      (node (ref "P6") (pin "15") (pinfunction "15_15") (pintype "passive"))
      (node (ref "P6") (pin "16") (pinfunction "16_16") (pintype "passive"))
      (node (ref "U1") (pin "50") (pinfunction "JTDI/PA15_50") (pintype "passive"))
    )
    (net (code "33") (name "/PB1") (class "Default")
      (node (ref "P4") (pin "3") (pinfunction "3_3") (pintype "passive"))
      (node (ref "P4") (pin "4") (pinfunction "4_4") (pintype "passive"))
      (node (ref "U1") (pin "27") (pinfunction "PB1/IN9/T3C4_27") (pintype "passive"))
    )
    (net (code "34") (name "/PB3") (class "Default")
      (node (ref "P8") (pin "1") (pinfunction "1_1") (pintype "passive"))
      (node (ref "P8") (pin "2") (pinfunction "2_2") (pintype "passive"))
      (node (ref "U1") (pin "55") (pinfunction "JTDO/PB3_55") (pintype "passive"))
    )
    (net (code "35") (name "/PB4") (class "Default")
      (node (ref "P8") (pin "3") (pinfunction "3_3") (pintype "passive"))
      (node (ref "P8") (pin "4") (pinfunction "4_4") (pintype "passive"))
      (node (ref "U1") (pin "56") (pinfunction "JNTRST/PB4_56") (pintype "passive"))
    )
    (net (code "36") (name "/PB8") (class "Default")
      (node (ref "P8") (pin "11") (pinfunction "11_11") (pintype "passive"))
      (node (ref "P8") (pin "12") (pinfunction "12_12") (pintype "passive"))
      (node (ref "U1") (pin "61") (pinfunction "T4C3/SDIO4PB8_61") (pintype "passive"))
      (node (ref "U2") (pin "4") (pinfunction "R_4") (pintype "passive"))
    )
    (net (code "37") (name "/PB9") (class "Default")
      (node (ref "P8") (pin "13") (pinfunction "13_13") (pintype "passive"))
      (node (ref "P8") (pin "14") (pinfunction "14_14") (pintype "passive"))
      (node (ref "U1") (pin "62") (pinfunction "SDIO5/PB9_62") (pintype "passive"))
      (node (ref "U2") (pin "1") (pinfunction "D_1") (pintype "passive"))
    )
    (net (code "38") (name "/PB14") (class "Default")
      (node (ref "P4") (pin "15") (pinfunction "15_15") (pintype "passive"))
      (node (ref "P4") (pin "16") (pinfunction "16_16") (pintype "passive"))
      (node (ref "U1") (pin "35") (pinfunction "MISO2/PB14_35") (pintype "passive"))
    )
    (net (code "39") (name "/PC0") (class "Default")
      (node (ref "P5") (pin "1") (pinfunction "1_1") (pintype "passive"))
      (node (ref "P5") (pin "2") (pinfunction "2_2") (pintype "passive"))
      (node (ref "U1") (pin "8") (pinfunction "PC0/IN10_8") (pintype "passive"))
    )
    (net (code "40") (name "/PC1") (class "Default")
      (node (ref "P5") (pin "3") (pinfunction "3_3") (pintype "passive"))
      (node (ref "P5") (pin "4") (pinfunction "4_4") (pintype "passive"))
      (node (ref "U1") (pin "9") (pinfunction "PC1/IN11_9") (pintype "passive"))
    )
    (net (code "41") (name "/PC2") (class "Default")
      (node (ref "P5") (pin "5") (pinfunction "5_5") (pintype "passive"))
      (node (ref "P5") (pin "6") (pinfunction "6_6") (pintype "passive"))
      (node (ref "U1") (pin "10") (pinfunction "PC2/IN12_10") (pintype "passive"))
    )
    (net (code "42") (name "/PC3") (class "Default")
      (node (ref "P5") (pin "7") (pinfunction "7_7") (pintype "passive"))
      (node (ref "P5") (pin "8") (pinfunction "8_8") (pintype "passive"))
      (node (ref "U1") (pin "11") (pinfunction "PC3/IN13_11") (pintype "passive"))
    )
    (net (code "43") (name "/PC5") (class "Default")
      (node (ref "J3") (pin "1") (pinfunction "1_1") (pintype "passive"))
      (node (ref "K3") (pin "2") (pinfunction "2_2") (pintype "passive"))
      (node (ref "P5") (pin "11") (pinfunction "11_11") (pintype "passive"))
      (node (ref "P5") (pin "12") (pinfunction "12_12") (pintype "passive"))
      (node (ref "U1") (pin "25") (pinfunction "PC5/IN15_25") (pintype "passive"))
    )
    (net (code "44") (name "/PC7") (class "Default")
      (node (ref "P24") (pin "5") (pinfunction "5_5") (pintype "passive"))
      (node (ref "P24") (pin "6") (pinfunction "6_6") (pintype "passive"))
      (node (ref "U1") (pin "38") (pinfunction "MCK3/SDIO7/PC7_38") (pintype "passive"))
    )
    (net (code "45") (name "/PC8") (class "Default")
      (node (ref "P24") (pin "3") (pinfunction "3_3") (pintype "passive"))
      (node (ref "P24") (pin "4") (pinfunction "4_4") (pintype "passive"))
      (node (ref "R19") (pin "2") (pinfunction "2_2") (pintype "passive"))
      (node (ref "SD1") (pin "7") (pinfunction "7_7") (pintype "passive"))
      (node (ref "U1") (pin "39") (pinfunction "SDIO0/T8C3/PC8_39") (pintype "passive"))
    )
    (net (code "46") (name "/PC9") (class "Default")
      (node (ref "P24") (pin "1") (pinfunction "1_1") (pintype "passive"))
      (node (ref "P24") (pin "2") (pinfunction "2_2") (pintype "passive"))
      (node (ref "R18") (pin "2") (pinfunction "2_2") (pintype "passive"))
      (node (ref "SD1") (pin "8") (pinfunction "8_8") (pintype "passive"))
      (node (ref "U1") (pin "40") (pinfunction "SDIO1/T8C4PC9_40") (pintype "passive"))
    )
    (net (code "47") (name "/PC10") (class "Default")
      (node (ref "P5") (pin "13") (pinfunction "13_13") (pintype "passive"))
      (node (ref "P5") (pin "14") (pinfunction "14_14") (pintype "passive"))
      (node (ref "R20") (pin "2") (pinfunction "2_2") (pintype "passive"))
      (node (ref "SD1") (pin "9") (pinfunction "9_9") (pintype "passive"))
      (node (ref "U1") (pin "51") (pinfunction "TXD4/SDIO2/PC10_51") (pintype "passive"))
    )
    (net (code "48") (name "/PC11") (class "Default")
      (node (ref "P5") (pin "15") (pinfunction "15_15") (pintype "passive"))
      (node (ref "P5") (pin "16") (pinfunction "16_16") (pintype "passive"))
      (node (ref "R22") (pin "2") (pinfunction "2_2") (pintype "passive"))
      (node (ref "SD1") (pin "1") (pinfunction "1_1") (pintype "passive"))
      (node (ref "U1") (pin "52") (pinfunction "RXD4/SDIO3/PC11_52") (pintype "passive"))
    )
    (net (code "49") (name "/PC12") (class "Default")
      (node (ref "P5") (pin "17") (pinfunction "17_17") (pintype "passive"))
      (node (ref "P5") (pin "18") (pinfunction "18_18") (pintype "passive"))
      (node (ref "SD1") (pin "5") (pinfunction "5_5") (pintype "passive"))
      (node (ref "U1") (pin "53") (pinfunction "TXD5/SDCK/PC12_53") (pintype "passive"))
    )
    (net (code "50") (name "/PC13") (class "Default")
      (node (ref "P5") (pin "19") (pinfunction "19_19") (pintype "passive"))
      (node (ref "P5") (pin "20") (pinfunction "20_20") (pintype "passive"))
      (node (ref "U1") (pin "2") (pinfunction "TAMPER-RTC/PC13_2") (pintype "passive"))
    )
    (net (code "51") (name "/PC14") (class "Default")
      (node (ref "C4") (pin "2") (pinfunction "2_2") (pintype "passive"))
      (node (ref "U1") (pin "3") (pinfunction "OSC32I/PC14_3") (pintype "passive"))
      (node (ref "Y1") (pin "1") (pinfunction "OSC1_1") (pintype "passive"))
    )
    (net (code "52") (name "/PC15") (class "Default")
      (node (ref "C5") (pin "2") (pinfunction "2_2") (pintype "passive"))
      (node (ref "U1") (pin "4") (pinfunction "OSC32O/PC15_4") (pintype "passive"))
      (node (ref "Y1") (pin "2") (pinfunction "OSC2_2") (pintype "passive"))
    )
    (net (code "53") (name "/PD2") (class "Default")
      (node (ref "P5") (pin "21") (pinfunction "21_21") (pintype "passive"))
      (node (ref "P5") (pin "22") (pinfunction "22_22") (pintype "passive"))
      (node (ref "R23") (pin "2") (pinfunction "2_2") (pintype "passive"))
      (node (ref "SD1") (pin "2") (pinfunction "2_2") (pintype "passive"))
      (node (ref "U1") (pin "54") (pinfunction "RXD5/SDCMD/PD2_54") (pintype "passive"))
    )
    (net (code "54") (name "/RESET") (class "Default")
      (node (ref "C2") (pin "1") (pinfunction "1_1") (pintype "passive"))
      (node (ref "D1") (pin "1") (pinfunction "A_1") (pintype "passive"))
      (node (ref "K1") (pin "1") (pinfunction "1_1") (pintype "passive"))
      (node (ref "R1") (pin "2") (pinfunction "2_2") (pintype "passive"))
      (node (ref "U1") (pin "7") (pinfunction "NRST_7") (pintype "passive"))
    )
    (net (code "55") (name "/RXD") (class "Default")
      (node (ref "P12") (pin "1") (pinfunction "1_1") (pintype "passive"))
      (node (ref "U8") (pin "2") (pinfunction "TX_2") (pintype "passive"))
    )
    (net (code "56") (name "/TXD") (class "Default")
      (node (ref "P12") (pin "2") (pinfunction "2_2") (pintype "passive"))
      (node (ref "U8") (pin "3") (pinfunction "RX_3") (pintype "passive"))
    )
    (net (code "57") (name "/VCC5V") (class "Default")
      (node (ref "C22") (pin "2") (pinfunction "2_2") (pintype "passive"))
      (node (ref "C3") (pin "2") (pinfunction "2_2") (pintype "passive"))
      (node (ref "C30") (pin "2") (pinfunction "2_2") (pintype "passive"))
      (node (ref "C31") (pin "2") (pinfunction "2_2") (pintype "passive"))
      (node (ref "F1") (pin "1") (pinfunction "1_1") (pintype "passive"))
      (node (ref "J3") (pin "4") (pinfunction "4_4") (pintype "passive"))
      (node (ref "U2") (pin "3") (pinfunction "VCC_3") (pintype "passive"))
      (node (ref "U7") (pin "3") (pinfunction "IN_3") (pintype "power_in"))
      (node (ref "U8") (pin "16") (pinfunction "VCC_16") (pintype "passive"))
    )
    (net (code "58") (name "GND") (class "Default")
      (node (ref "BT1") (pin "2") (pinfunction "-_2") (pintype "passive"))
      (node (ref "C1") (pin "2") (pinfunction "2_2") (pintype "passive"))
      (node (ref "C10") (pin "2") (pinfunction "2_2") (pintype "passive"))
      (node (ref "C12") (pin "2") (pinfunction "2_2") (pintype "passive"))
      (node (ref "C14") (pin "2") (pinfunction "2_2") (pintype "passive"))
      (node (ref "C15") (pin "2") (pinfunction "2_2") (pintype "passive"))
      (node (ref "C16") (pin "2") (pinfunction "2_2") (pintype "passive"))
      (node (ref "C17") (pin "2") (pinfunction "2_2") (pintype "passive"))
      (node (ref "C18") (pin "2") (pinfunction "2_2") (pintype "passive"))
      (node (ref "C19") (pin "2") (pinfunction "2_2") (pintype "passive"))
      (node (ref "C2") (pin "2") (pinfunction "2_2") (pintype "passive"))
      (node (ref "C20") (pin "1") (pinfunction "1_1") (pintype "passive"))
      (node (ref "C21") (pin "2") (pinfunction "2_2") (pintype "passive"))
      (node (ref "C22") (pin "1") (pinfunction "1_1") (pintype "passive"))
      (node (ref "C23") (pin "2") (pinfunction "2_2") (pintype "passive"))
      (node (ref "C24") (pin "2") (pinfunction "2_2") (pintype "passive"))
      (node (ref "C25") (pin "2") (pinfunction "2_2") (pintype "passive"))
      (node (ref "C26") (pin "2") (pinfunction "2_2") (pintype "passive"))
      (node (ref "C27") (pin "2") (pinfunction "2_2") (pintype "passive"))
      (node (ref "C28") (pin "1") (pinfunction "1_1") (pintype "passive"))
      (node (ref "C29") (pin "1") (pinfunction "1_1") (pintype "passive"))
      (node (ref "C3") (pin "1") (pinfunction "1_1") (pintype "passive"))
      (node (ref "C30") (pin "1") (pinfunction "1_1") (pintype "passive"))
      (node (ref "C31") (pin "1") (pinfunction "1_1") (pintype "passive"))
      (node (ref "C4") (pin "1") (pinfunction "1_1") (pintype "passive"))
      (node (ref "C5") (pin "1") (pinfunction "1_1") (pintype "passive"))
      (node (ref "C6") (pin "1") (pinfunction "1_1") (pintype "passive"))
      (node (ref "C7") (pin "1") (pinfunction "1_1") (pintype "passive"))
      (node (ref "C8") (pin "1") (pinfunction "1_1") (pintype "passive"))
      (node (ref "C9") (pin "1") (pinfunction "1_1") (pintype "passive"))
      (node (ref "J1") (pin "1") (pinfunction "GND_1") (pintype "passive"))
      (node (ref "J2") (pin "4") (pinfunction "GND_4") (pintype "passive"))
      (node (ref "J3") (pin "3") (pinfunction "3_3") (pintype "passive"))
      (node (ref "J4") (pin "4") (pinfunction "GND_4") (pintype "passive"))
      (node (ref "K1") (pin "2") (pinfunction "2_2") (pintype "passive"))
      (node (ref "K3") (pin "1") (pinfunction "1_1") (pintype "passive"))
      (node (ref "K4") (pin "1") (pinfunction "1_1") (pintype "passive"))
      (node (ref "LED3") (pin "2") (pinfunction "2_2") (pintype "passive"))
      (node (ref "P1") (pin "2") (pinfunction "2_2") (pintype "passive"))
      (node (ref "P10") (pin "1") (pinfunction "1_1") (pintype "passive"))
      (node (ref "P11") (pin "1") (pinfunction "1_1") (pintype "passive"))
      (node (ref "P14") (pin "8") (pinfunction "8_8") (pintype "passive"))
      (node (ref "P15") (pin "5") (pinfunction "5_5") (pintype "passive"))
      (node (ref "P15") (pin "6") (pinfunction "6_6") (pintype "passive"))
      (node (ref "P7") (pin "1") (pinfunction "1_1") (pintype "passive"))
      (node (ref "R10") (pin "1") (pinfunction "1_1") (pintype "passive"))
      (node (ref "R14") (pin "1") (pinfunction "1_1") (pintype "passive"))
      (node (ref "R7") (pin "1") (pinfunction "1_1") (pintype "passive"))
      (node (ref "SD1") (pin "3") (pinfunction "3_3") (pintype "passive"))
      (node (ref "SD1") (pin "6") (pinfunction "6_6") (pintype "passive"))
      (node (ref "SD2") (pin "3") (pinfunction "3_3") (pintype "passive"))
      (node (ref "SD2") (pin "6") (pinfunction "6_6") (pintype "passive"))
      (node (ref "U1") (pin "12") (pinfunction "VSSA_12") (pintype "passive"))
      (node (ref "U1") (pin "18") (pinfunction "VSS4_18") (pintype "passive"))
      (node (ref "U1") (pin "31") (pinfunction "VSS1_31") (pintype "passive"))
      (node (ref "U1") (pin "47") (pinfunction "VSS2_47") (pintype "passive"))
      (node (ref "U1") (pin "63") (pinfunction "VSS3_63") (pintype "passive"))
      (node (ref "U2") (pin "2") (pinfunction "GND_2") (pintype "passive"))
      (node (ref "U2") (pin "8") (pinfunction "RS_8") (pintype "passive"))
      (node (ref "U3") (pin "8") (pinfunction "AGND_8") (pintype "passive"))
      (node (ref "U4") (pin "8") (pinfunction "GND_8") (pintype "passive"))
      (node (ref "U5") (pin "1") (pinfunction "1_1") (pintype "passive"))
      (node (ref "U6") (pin "4") (pinfunction "GND_4") (pintype "passive"))
      (node (ref "U7") (pin "1") (pinfunction "GND_1") (pintype "power_in"))
      (node (ref "U8") (pin "1") (pinfunction "GND_1") (pintype "passive"))
    )
    (net (code "59") (name "Net-(BT1-+)") (class "Default")
      (node (ref "BT1") (pin "1") (pinfunction "+_1") (pintype "passive"))
      (node (ref "D2") (pin "1") (pinfunction "A_1") (pintype "passive"))
    )
    (net (code "60") (name "Net-(C11-Pad2)") (class "Default")
      (node (ref "C11") (pin "2") (pinfunction "2_2") (pintype "passive"))
      (node (ref "R4") (pin "2") (pinfunction "2_2") (pintype "passive"))
      (node (ref "R7") (pin "2") (pinfunction "2_2") (pintype "passive"))
    )
    (net (code "61") (name "Net-(C13-Pad2)") (class "Default")
      (node (ref "C13") (pin "2") (pinfunction "2_2") (pintype "passive"))
      (node (ref "R10") (pin "2") (pinfunction "2_2") (pintype "passive"))
      (node (ref "R9") (pin "1") (pinfunction "1_1") (pintype "passive"))
    )
    (net (code "62") (name "Net-(D1-K)") (class "Default")
      (node (ref "D1") (pin "2") (pinfunction "K_2") (pintype "passive"))
      (node (ref "Q2") (pin "1") (pinfunction "C_1") (pintype "passive"))
      (node (ref "R32") (pin "2") (pinfunction "2_2") (pintype "passive"))
    )
    (net (code "63") (name "Net-(D2-K)") (class "Default")
      (node (ref "D2") (pin "2") (pinfunction "K_2") (pintype "passive"))
      (node (ref "D3") (pin "2") (pinfunction "K_2") (pintype "passive"))
      (node (ref "U1") (pin "1") (pinfunction "VBAT_1") (pintype "passive"))
    )
    (net (code "64") (name "Net-(J1-L)") (class "Default")
      (node (ref "C17") (pin "1") (pinfunction "1_1") (pintype "passive"))
      (node (ref "J1") (pin "2") (pinfunction "L_2") (pintype "passive"))
      (node (ref "R9") (pin "2") (pinfunction "2_2") (pintype "passive"))
    )
    (net (code "65") (name "Net-(J1-R)") (class "Default")
      (node (ref "C18") (pin "1") (pinfunction "1_1") (pintype "passive"))
      (node (ref "J1") (pin "3") (pinfunction "R_3") (pintype "passive"))
      (node (ref "R4") (pin "1") (pinfunction "1_1") (pintype "passive"))
    )
    (net (code "66") (name "Net-(J2-DATA+)") (class "Default")
      (node (ref "J2") (pin "3") (pinfunction "DATA+_3") (pintype "passive"))
      (node (ref "R5") (pin "2") (pinfunction "2_2") (pintype "passive"))
      (node (ref "R6") (pin "2") (pinfunction "2_2") (pintype "passive"))
    )
    (net (code "67") (name "Net-(J2-DATA-)") (class "Default")
      (node (ref "J2") (pin "2") (pinfunction "DATA-_2") (pintype "passive"))
      (node (ref "R8") (pin "2") (pinfunction "2_2") (pintype "passive"))
    )
    (net (code "68") (name "Net-(J4-DATA+)") (class "Default")
      (node (ref "J4") (pin "3") (pinfunction "DATA+_3") (pintype "passive"))
      (node (ref "R28") (pin "1") (pinfunction "1_1") (pintype "passive"))
      (node (ref "U8") (pin "5") (pinfunction "D+_5") (pintype "passive"))
    )
    (net (code "69") (name "Net-(J4-DATA-)") (class "Default")
      (node (ref "J4") (pin "2") (pinfunction "DATA-_2") (pintype "passive"))
      (node (ref "U8") (pin "6") (pinfunction "D-_6") (pintype "passive"))
    )
    (net (code "70") (name "Net-(LED1-Pad1)") (class "Default")
      (node (ref "LED1") (pin "1") (pinfunction "1_1") (pintype "passive"))
      (node (ref "R15") (pin "2") (pinfunction "2_2") (pintype "passive"))
    )
    (net (code "71") (name "Net-(LED2-Pad1)") (class "Default")
      (node (ref "LED2") (pin "1") (pinfunction "1_1") (pintype "passive"))
      (node (ref "R17") (pin "2") (pinfunction "2_2") (pintype "passive"))
    )
    (net (code "72") (name "Net-(LED3-Pad1)") (class "Default")
      (node (ref "LED3") (pin "1") (pinfunction "1_1") (pintype "passive"))
      (node (ref "R21") (pin "2") (pinfunction "2_2") (pintype "passive"))
    )
    (net (code "73") (name "Net-(P15-Pad3)") (class "Default")
      (node (ref "P15") (pin "3") (pinfunction "3_3") (pintype "passive"))
      (node (ref "R12") (pin "2") (pinfunction "2_2") (pintype "passive"))
    )
    (net (code "74") (name "Net-(P15-Pad4)") (class "Default")
      (node (ref "P15") (pin "4") (pinfunction "4_4") (pintype "passive"))
      (node (ref "R13") (pin "1") (pinfunction "1_1") (pintype "passive"))
    )
    (net (code "75") (name "Net-(Q1-B)") (class "Default")
      (node (ref "Q1") (pin "2") (pinfunction "B_2") (pintype "passive"))
      (node (ref "R30") (pin "1") (pinfunction "1_1") (pintype "passive"))
    )
    (net (code "76") (name "Net-(Q1-C)") (class "Default")
      (node (ref "Q1") (pin "1") (pinfunction "C_1") (pintype "passive"))
      (node (ref "R25") (pin "1") (pinfunction "1_1") (pintype "passive"))
    )
    (net (code "77") (name "Net-(Q2-B)") (class "Default")
      (node (ref "Q2") (pin "2") (pinfunction "B_2") (pintype "passive"))
      (node (ref "R31") (pin "1") (pinfunction "1_1") (pintype "passive"))
    )
    (net (code "78") (name "Net-(Q2-E)") (class "Default")
      (node (ref "Q2") (pin "3") (pinfunction "E_3") (pintype "passive"))
      (node (ref "R30") (pin "2") (pinfunction "2_2") (pintype "passive"))
      (node (ref "U8") (pin "14") (pinfunction "RTS#_14") (pintype "passive"))
    )
    (net (code "79") (name "Net-(R16-Pad1)") (class "Default")
      (node (ref "R16") (pin "1") (pinfunction "1_1") (pintype "passive"))
      (node (ref "U5") (pin "8") (pinfunction "8_8") (pintype "passive"))
    )
    (net (code "80") (name "Net-(U1-OSCI)") (class "Default")
      (node (ref "C6") (pin "2") (pinfunction "2_2") (pintype "passive"))
      (node (ref "R3") (pin "1") (pinfunction "1_1") (pintype "passive"))
      (node (ref "U1") (pin "5") (pinfunction "OSCI_5") (pintype "passive"))
      (node (ref "Y2") (pin "1") (pinfunction "OSC1_1") (pintype "passive"))
    )
    (net (code "81") (name "Net-(U1-OSCO)") (class "Default")
      (node (ref "C7") (pin "2") (pinfunction "2_2") (pintype "passive"))
      (node (ref "R3") (pin "2") (pinfunction "2_2") (pintype "passive"))
      (node (ref "U1") (pin "6") (pinfunction "OSCO_6") (pintype "passive"))
      (node (ref "Y2") (pin "2") (pinfunction "OSC2_2") (pintype "passive"))
    )
    (net (code "82") (name "Net-(U2-CANH)") (class "Default")
      (node (ref "P2") (pin "1") (pinfunction "1_1") (pintype "passive"))
      (node (ref "R2") (pin "1") (pinfunction "1_1") (pintype "passive"))
      (node (ref "U2") (pin "7") (pinfunction "CANH_7") (pintype "passive"))
    )
    (net (code "83") (name "Net-(U2-CANL)") (class "Default")
      (node (ref "P2") (pin "2") (pinfunction "2_2") (pintype "passive"))
      (node (ref "R2") (pin "2") (pinfunction "2_2") (pintype "passive"))
      (node (ref "U2") (pin "6") (pinfunction "CANL_6") (pintype "passive"))
    )
    (net (code "84") (name "Net-(U3-AOUTL)") (class "Default")
      (node (ref "C13") (pin "1") (pinfunction "1_1") (pintype "passive"))
      (node (ref "U3") (pin "7") (pinfunction "AOUTL_7") (pintype "passive"))
    )
    (net (code "85") (name "Net-(U3-AOUTR)") (class "Default")
      (node (ref "C11") (pin "1") (pinfunction "1_1") (pintype "passive"))
      (node (ref "U3") (pin "10") (pinfunction "AOUTR_10") (pintype "passive"))
    )
    (net (code "86") (name "Net-(U3-FILT+)") (class "Default")
      (node (ref "C14") (pin "1") (pinfunction "1_1") (pintype "passive"))
      (node (ref "U3") (pin "6") (pinfunction "FILT+_6") (pintype "passive"))
    )
    (net (code "87") (name "Net-(U3-VQ)") (class "Default")
      (node (ref "C15") (pin "1") (pinfunction "1_1") (pintype "passive"))
      (node (ref "C16") (pin "1") (pinfunction "1_1") (pintype "passive"))
      (node (ref "U3") (pin "5") (pinfunction "VQ_5") (pintype "passive"))
    )
    (net (code "88") (name "Net-(U4-ADC)") (class "Default")
      (node (ref "P13") (pin "7") (pinfunction "7_7") (pintype "passive"))
      (node (ref "U4") (pin "21") (pinfunction "ADC_21") (pintype "passive"))
    )
    (net (code "89") (name "Net-(U4-CS0)") (class "Default")
      (node (ref "P16") (pin "6") (pinfunction "6_6") (pintype "passive"))
      (node (ref "U4") (pin "14") (pinfunction "CS0_14") (pintype "passive"))
    )
    (net (code "90") (name "Net-(U4-EN)") (class "Default")
      (node (ref "P13") (pin "6") (pinfunction "6_6") (pintype "passive"))
      (node (ref "R11") (pin "2") (pinfunction "2_2") (pintype "passive"))
      (node (ref "U4") (pin "20") (pinfunction "EN_20") (pintype "passive"))
    )
    (net (code "91") (name "Net-(U4-IO0)") (class "Default")
      (node (ref "P14") (pin "5") (pinfunction "5_5") (pintype "passive"))
      (node (ref "U4") (pin "5") (pinfunction "IO0_5") (pintype "passive"))
    )
    (net (code "92") (name "Net-(U4-IO2)") (class "Default")
      (node (ref "P14") (pin "6") (pinfunction "6_6") (pintype "passive"))
      (node (ref "U4") (pin "6") (pinfunction "IO2_6") (pintype "passive"))
    )
    (net (code "93") (name "Net-(U4-IO4)") (class "Default")
      (node (ref "P14") (pin "4") (pinfunction "4_4") (pintype "passive"))
      (node (ref "U4") (pin "4") (pinfunction "IO4_4") (pintype "passive"))
    )
    (net (code "94") (name "Net-(U4-IO5)") (class "Default")
      (node (ref "P14") (pin "3") (pinfunction "3_3") (pintype "passive"))
      (node (ref "U4") (pin "3") (pinfunction "IO5_3") (pintype "passive"))
    )
    (net (code "95") (name "Net-(U4-IO9)") (class "Default")
      (node (ref "P16") (pin "4") (pinfunction "4_4") (pintype "passive"))
      (node (ref "U4") (pin "12") (pinfunction "IO9_12") (pintype "passive"))
    )
    (net (code "96") (name "Net-(U4-IO10)") (class "Default")
      (node (ref "P16") (pin "3") (pinfunction "3_3") (pintype "passive"))
      (node (ref "U4") (pin "11") (pinfunction "IO10_11") (pintype "passive"))
    )
    (net (code "97") (name "Net-(U4-IO12)") (class "Default")
      (node (ref "P13") (pin "3") (pinfunction "3_3") (pintype "passive"))
      (node (ref "U4") (pin "17") (pinfunction "IO12_17") (pintype "passive"))
    )
    (net (code "98") (name "Net-(U4-IO13)") (class "Default")
      (node (ref "P13") (pin "2") (pinfunction "2_2") (pintype "passive"))
      (node (ref "U4") (pin "16") (pinfunction "IO13_16") (pintype "passive"))
    )
    (net (code "99") (name "Net-(U4-IO14)") (class "Default")
      (node (ref "P13") (pin "4") (pinfunction "4_4") (pintype "passive"))
      (node (ref "U4") (pin "18") (pinfunction "IO14_18") (pintype "passive"))
    )
    (net (code "100") (name "Net-(U4-IO15)") (class "Default")
      (node (ref "P14") (pin "7") (pinfunction "7_7") (pintype "passive"))
      (node (ref "R14") (pin "2") (pinfunction "2_2") (pintype "passive"))
      (node (ref "U4") (pin "7") (pinfunction "IO15_7") (pintype "passive"))
    )
    (net (code "101") (name "Net-(U4-IO16)") (class "Default")
      (node (ref "P13") (pin "5") (pinfunction "5_5") (pintype "passive"))
      (node (ref "U4") (pin "19") (pinfunction "IO16_19") (pintype "passive"))
    )
    (net (code "102") (name "Net-(U4-MISO)") (class "Default")
      (node (ref "P16") (pin "5") (pinfunction "5_5") (pintype "passive"))
      (node (ref "U4") (pin "13") (pinfunction "MISO_13") (pintype "passive"))
    )
    (net (code "103") (name "Net-(U4-MOSI)") (class "Default")
      (node (ref "P16") (pin "2") (pinfunction "2_2") (pintype "passive"))
      (node (ref "U4") (pin "10") (pinfunction "MOSI_10") (pintype "passive"))
    )
    (net (code "104") (name "Net-(U4-RST)") (class "Default")
      (node (ref "P13") (pin "8") (pinfunction "8_8") (pintype "passive"))
      (node (ref "U4") (pin "22") (pinfunction "RST_22") (pintype "passive"))
    )
    (net (code "105") (name "Net-(U4-SCLCK)") (class "Default")
      (node (ref "P16") (pin "1") (pinfunction "1_1") (pintype "passive"))
      (node (ref "U4") (pin "9") (pinfunction "SCLCK_9") (pintype "passive"))
    )
    (net (code "106") (name "Net-(U8-DTR#)") (class "Default")
      (node (ref "R31") (pin "2") (pinfunction "2_2") (pintype "passive"))
      (node (ref "U8") (pin "13") (pinfunction "DTR#_13") (pintype "passive"))
    )
    (net (code "107") (name "Net-(U8-V3)") (class "Default")
      (node (ref "C26") (pin "1") (pinfunction "1_1") (pintype "passive"))
      (node (ref "U8") (pin "4") (pinfunction "V3_4") (pintype "passive"))
    )
    (net (code "108") (name "Net-(U8-X0)") (class "Default")
      (node (ref "C28") (pin "2") (pinfunction "2_2") (pintype "passive"))
      (node (ref "U8") (pin "8") (pinfunction "X0_8") (pintype "passive"))
      (node (ref "Y3") (pin "1") (pinfunction "OSC1_1") (pintype "passive"))
    )
    (net (code "109") (name "Net-(U8-XI)") (class "Default")
      (node (ref "C29") (pin "2") (pinfunction "2_2") (pintype "passive"))
      (node (ref "U8") (pin "7") (pinfunction "XI_7") (pintype "passive"))
      (node (ref "Y3") (pin "2") (pinfunction "OSC2_2") (pintype "passive"))
    )
    (net (code "110") (name "VCC") (class "Default")
      (node (ref "C1") (pin "1") (pinfunction "1_1") (pintype "passive"))
      (node (ref "C10") (pin "1") (pinfunction "1_1") (pintype "passive"))
      (node (ref "C12") (pin "1") (pinfunction "1_1") (pintype "passive"))
      (node (ref "C19") (pin "1") (pinfunction "1_1") (pintype "passive"))
      (node (ref "C20") (pin "2") (pinfunction "2_2") (pintype "passive"))
      (node (ref "C21") (pin "1") (pinfunction "1_1") (pintype "passive"))
      (node (ref "C23") (pin "1") (pinfunction "1_1") (pintype "passive"))
      (node (ref "C24") (pin "1") (pinfunction "1_1") (pintype "passive"))
      (node (ref "C25") (pin "1") (pinfunction "1_1") (pintype "passive"))
      (node (ref "C27") (pin "1") (pinfunction "1_1") (pintype "passive"))
      (node (ref "C8") (pin "2") (pinfunction "2_2") (pintype "passive"))
      (node (ref "C9") (pin "2") (pinfunction "2_2") (pintype "passive"))
      (node (ref "D3") (pin "1") (pinfunction "A_1") (pintype "passive"))
      (node (ref "K2") (pin "1") (pinfunction "1_1") (pintype "passive"))
      (node (ref "P1") (pin "1") (pinfunction "1_1") (pintype "passive"))
      (node (ref "P11") (pin "4") (pinfunction "4_4") (pintype "passive"))
      (node (ref "P13") (pin "1") (pinfunction "1_1") (pintype "passive"))
      (node (ref "P15") (pin "1") (pinfunction "1_1") (pintype "passive"))
      (node (ref "P15") (pin "2") (pinfunction "2_2") (pintype "passive"))
      (node (ref "Q1") (pin "3") (pinfunction "E_3") (pintype "passive"))
      (node (ref "R1") (pin "1") (pinfunction "1_1") (pintype "passive"))
      (node (ref "R11") (pin "1") (pinfunction "1_1") (pintype "passive"))
      (node (ref "R15") (pin "1") (pinfunction "1_1") (pintype "passive"))
      (node (ref "R17") (pin "1") (pinfunction "1_1") (pintype "passive"))
      (node (ref "R18") (pin "1") (pinfunction "1_1") (pintype "passive"))
      (node (ref "R19") (pin "1") (pinfunction "1_1") (pintype "passive"))
      (node (ref "R20") (pin "1") (pinfunction "1_1") (pintype "passive"))
      (node (ref "R21") (pin "1") (pinfunction "1_1") (pintype "passive"))
      (node (ref "R22") (pin "1") (pinfunction "1_1") (pintype "passive"))
      (node (ref "R23") (pin "1") (pinfunction "1_1") (pintype "passive"))
      (node (ref "R24") (pin "1") (pinfunction "1_1") (pintype "passive"))
      (node (ref "R26") (pin "1") (pinfunction "1_1") (pintype "passive"))
      (node (ref "R27") (pin "1") (pinfunction "1_1") (pintype "passive"))
      (node (ref "R28") (pin "2") (pinfunction "2_2") (pintype "passive"))
      (node (ref "R29") (pin "1") (pinfunction "1_1") (pintype "passive"))
      (node (ref "R32") (pin "1") (pinfunction "1_1") (pintype "passive"))
      (node (ref "R5") (pin "1") (pinfunction "1_1") (pintype "passive"))
      (node (ref "SD1") (pin "4") (pinfunction "4_4") (pintype "passive"))
      (node (ref "SD2") (pin "4") (pinfunction "4_4") (pintype "passive"))
      (node (ref "U1") (pin "13") (pinfunction "VDDA_13") (pintype "passive"))
      (node (ref "U1") (pin "19") (pinfunction "VDD4_19") (pintype "passive"))
      (node (ref "U1") (pin "32") (pinfunction "VDD1_32") (pintype "passive"))
      (node (ref "U1") (pin "48") (pinfunction "VDD2_48") (pintype "passive"))
      (node (ref "U1") (pin "64") (pinfunction "VDD3_64") (pintype "passive"))
      (node (ref "U3") (pin "9") (pinfunction "VCC_9") (pintype "passive"))
      (node (ref "U4") (pin "15") (pinfunction "VCC_15") (pintype "passive"))
      (node (ref "U5") (pin "2") (pinfunction "2_2") (pintype "passive"))
      (node (ref "U6") (pin "3") (pinfunction "WP#_3") (pintype "passive"))
      (node (ref "U6") (pin "7") (pinfunction "HOLD_7") (pintype "passive"))
      (node (ref "U6") (pin "8") (pinfunction "VCC_8") (pintype "passive"))
      (node (ref "U7") (pin "2") (pinfunction "OUT_2") (pintype "power_in"))
      (node (ref "U7") (pin "4") (pinfunction "OUT_4") (pintype "power_in"))
    )
    (net (code "111") (name "unconnected-(J3-Pad2)") (class "Default")
      (node (ref "J3") (pin "2") (pinfunction "2_2") (pintype "passive"))
    )
    (net (code "112") (name "unconnected-(J3-Pad6)") (class "Default")
      (node (ref "J3") (pin "6") (pinfunction "6_6") (pintype "passive"))
    )
    (net (code "113") (name "unconnected-(SD2-Pad8)") (class "Default")
      (node (ref "SD2") (pin "8") (pinfunction "8_8") (pintype "passive"))
    )
    (net (code "114") (name "unconnected-(SD2-Pad9)") (class "Default")
      (node (ref "SD2") (pin "9") (pinfunction "9_9") (pintype "passive"))
    )
    (net (code "115") (name "unconnected-(U2-VREF-Pad5)") (class "Default")
      (node (ref "U2") (pin "5") (pinfunction "VREF_5") (pintype "passive"))
    )
    (net (code "116") (name "unconnected-(U8-Pad9)") (class "Default")
      (node (ref "U8") (pin "9") (pinfunction "9_9") (pintype "passive"))
    )
    (net (code "117") (name "unconnected-(U8-Pad10)") (class "Default")
      (node (ref "U8") (pin "10") (pinfunction "10_10") (pintype "passive"))
    )
    (net (code "118") (name "unconnected-(U8-Pad11)") (class "Default")
      (node (ref "U8") (pin "11") (pinfunction "11_11") (pintype "passive"))
    )
    (net (code "119") (name "unconnected-(U8-Pad12)") (class "Default")
      (node (ref "U8") (pin "12") (pinfunction "12_12") (pintype "passive"))
    )
    (net (code "120") (name "unconnected-(U8-Pad15)") (class "Default")
      (node (ref "U8") (pin "15") (pinfunction "15_15") (pintype "passive"))
    )
  )
)
